# ECE411-Group6-V2.net
KiCad netlist of a schematic drawn in EAGLE
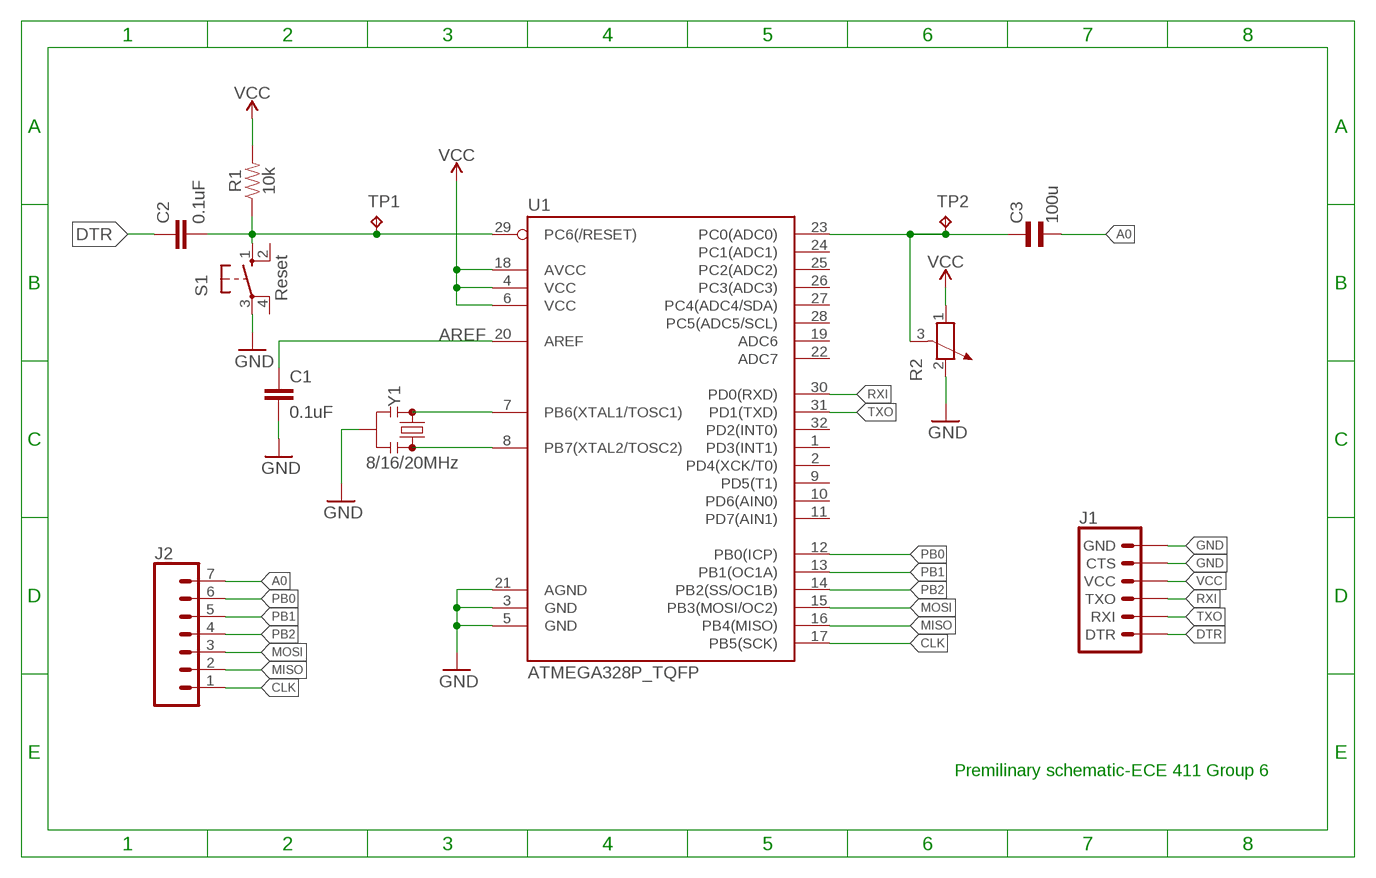
[diagram p0: schematic, sheet 1]

(export (version "E")
  (design (tool "Eeschema 10.0.6"))
  (components
    (comp (ref "C1")
      (value "0.1uF")
      (footprint "eagle-import:0603")
      (libsource (lib "eagle-import") (part "0.1UF-0603-25V-5%"))
    )
    (comp (ref "C2")
      (value "0.1uF")
      (footprint "eagle-import:0603")
      (libsource (lib "eagle-import") (part "0.1UF-0603-25V-5%"))
    )
    (comp (ref "C3")
      (value "100u")
      (footprint "eagle-import:EU25-10")
      (libsource (lib "eagle-import") (part "EL-BI25-10AXIAL"))
    )
    (comp (ref "J1")
      (value "6_PIN_SERIAL_TARGET")
      (footprint "eagle-import:1X06")
      (libsource (lib "eagle-import") (part "6_PIN_SERIAL_TARGET"))
    )
    (comp (ref "J2")
      (value "CONN_07")
      (footprint "eagle-import:1X07")
      (libsource (lib "eagle-import") (part "CONN_07"))
    )
    (comp (ref "R1")
      (value "10k")
      (footprint "eagle-import:0603")
      (libsource (lib "eagle-import") (part "10KOHM-0603-1/10W-1%"))
    )
    (comp (ref "R2")
      (value "POTENTIOMETER_PT-10")
      (footprint "eagle-import:PT-10")
      (libsource (lib "eagle-import") (part "POTENTIOMETER_PT-10"))
    )
    (comp (ref "S1")
      (value "Reset")
      (footprint "eagle-import:B3F-10XX")
      (fields (field (name "MPN") "B3F-1000"))
      (libsource (lib "eagle-import") (part "10-XX"))
    )
    (comp (ref "TP1")
      (value "TPB1,27")
      (footprint "eagle-import:B1,27")
      (libsource (lib "eagle-import") (part "TPB1,27"))
    )
    (comp (ref "TP2")
      (value "TPB1,27")
      (footprint "eagle-import:B1,27")
      (libsource (lib "eagle-import") (part "TPB1,27"))
    )
    (comp (ref "U1")
      (value "ATMEGA328P_TQFP")
      (footprint "eagle-import:TQFP32-08")
      (libsource (lib "eagle-import") (part "ATMEGA328P_TQFP"))
    )
    (comp (ref "Y1")
      (value "8/16/20MHz")
      (footprint "eagle-import:RESONATOR-SMD-3.2X1.3")
      (libsource (lib "eagle-import") (part "RESONATORSMD-3.2X1.3"))
    )
  )
  (nets
    (net (code "1") (name "/AREF") (class "Default")
      (node (ref "C1") (pin "1") (pinfunction "1_1") (pintype "passive"))
      (node (ref "U1") (pin "20") (pinfunction "AREF_20") (pintype "bidirectional"))
    )
    (net (code "2") (name "A0") (class "Default")
      (node (ref "C3") (pin "2") (pinfunction "2_2") (pintype "passive"))
      (node (ref "J2") (pin "7") (pinfunction "7_7") (pintype "passive"))
    )
    (net (code "3") (name "CLK") (class "Default")
      (node (ref "J2") (pin "1") (pinfunction "1_1") (pintype "passive"))
      (node (ref "U1") (pin "17") (pinfunction "PB5(SCK)_17") (pintype "bidirectional"))
    )
    (net (code "4") (name "DTR") (class "Default")
      (node (ref "C2") (pin "1") (pinfunction "1_1") (pintype "passive"))
      (node (ref "J1") (pin "1") (pinfunction "DTR_1") (pintype "passive"))
    )
    (net (code "5") (name "GND") (class "Default")
      (node (ref "C1") (pin "2") (pinfunction "2_2") (pintype "passive"))
      (node (ref "J1") (pin "5") (pinfunction "CTS_5") (pintype "passive"))
      (node (ref "J1") (pin "6") (pinfunction "GND_6") (pintype "passive"))
      (node (ref "R2") (pin "2") (pinfunction "2_2") (pintype "passive"))
      (node (ref "S1") (pin "3") (pinfunction "P_3") (pintype "passive"))
      (node (ref "U1") (pin "21") (pinfunction "AGND_21") (pintype "bidirectional"))
      (node (ref "U1") (pin "3") (pinfunction "GND_3") (pintype "bidirectional"))
      (node (ref "U1") (pin "5") (pinfunction "GND_5") (pintype "bidirectional"))
      (node (ref "Y1") (pin "2") (pinfunction "2_2") (pintype "passive"))
    )
    (net (code "6") (name "MISO") (class "Default")
      (node (ref "J2") (pin "2") (pinfunction "2_2") (pintype "passive"))
      (node (ref "U1") (pin "16") (pinfunction "PB4(MISO)_16") (pintype "bidirectional"))
    )
    (net (code "7") (name "MOSI") (class "Default")
      (node (ref "J2") (pin "3") (pinfunction "3_3") (pintype "passive"))
      (node (ref "U1") (pin "15") (pinfunction "PB3(MOSI/OC2)_15") (pintype "bidirectional"))
    )
    (net (code "8") (name "Net-(S1-S)") (class "Default")
      (node (ref "C2") (pin "2") (pinfunction "2_2") (pintype "passive"))
      (node (ref "R1") (pin "1") (pinfunction "1_1") (pintype "passive"))
      (node (ref "S1") (pin "1") (pinfunction "S_1") (pintype "passive"))
      (node (ref "TP1") (pin "TP") (pinfunction "TP_TP") (pintype "input"))
      (node (ref "U1") (pin "29") (pinfunction "PC6(/RESET)_29") (pintype "bidirectional"))
    )
    (net (code "9") (name "Net-(U1-PB6(XTAL1{slash}TOSC1))") (class "Default")
      (node (ref "U1") (pin "7") (pinfunction "PB6(XTAL1/TOSC1)_7") (pintype "bidirectional"))
      (node (ref "Y1") (pin "1") (pinfunction "1_1") (pintype "passive"))
    )
    (net (code "10") (name "Net-(U1-PB7(XTAL2{slash}TOSC2))") (class "Default")
      (node (ref "U1") (pin "8") (pinfunction "PB7(XTAL2/TOSC2)_8") (pintype "bidirectional"))
      (node (ref "Y1") (pin "3") (pinfunction "3_3") (pintype "passive"))
    )
    (net (code "11") (name "Net-(U1-PC0(ADC0))") (class "Default")
      (node (ref "C3") (pin "1") (pinfunction "1_1") (pintype "passive"))
      (node (ref "R2") (pin "3") (pinfunction "3_3") (pintype "passive"))
      (node (ref "TP2") (pin "TP") (pinfunction "TP_TP") (pintype "input"))
      (node (ref "U1") (pin "23") (pinfunction "PC0(ADC0)_23") (pintype "bidirectional"))
    )
    (net (code "12") (name "PB0") (class "Default")
      (node (ref "J2") (pin "6") (pinfunction "6_6") (pintype "passive"))
      (node (ref "U1") (pin "12") (pinfunction "PB0(ICP)_12") (pintype "bidirectional"))
    )
    (net (code "13") (name "PB1") (class "Default")
      (node (ref "J2") (pin "5") (pinfunction "5_5") (pintype "passive"))
      (node (ref "U1") (pin "13") (pinfunction "PB1(OC1A)_13") (pintype "bidirectional"))
    )
    (net (code "14") (name "PB2") (class "Default")
      (node (ref "J2") (pin "4") (pinfunction "4_4") (pintype "passive"))
      (node (ref "U1") (pin "14") (pinfunction "PB2(SS/OC1B)_14") (pintype "bidirectional"))
    )
    (net (code "15") (name "RXI") (class "Default")
      (node (ref "J1") (pin "3") (pinfunction "TXO_3") (pintype "passive"))
      (node (ref "U1") (pin "30") (pinfunction "PD0(RXD)_30") (pintype "bidirectional"))
    )
    (net (code "16") (name "TXO") (class "Default")
      (node (ref "J1") (pin "2") (pinfunction "RXI_2") (pintype "passive"))
      (node (ref "U1") (pin "31") (pinfunction "PD1(TXD)_31") (pintype "bidirectional"))
    )
    (net (code "17") (name "VCC") (class "Default")
      (node (ref "J1") (pin "4") (pinfunction "VCC_4") (pintype "passive"))
      (node (ref "R1") (pin "2") (pinfunction "2_2") (pintype "passive"))
      (node (ref "R2") (pin "1") (pinfunction "1_1") (pintype "passive"))
      (node (ref "U1") (pin "18") (pinfunction "AVCC_18") (pintype "bidirectional"))
      (node (ref "U1") (pin "4") (pinfunction "VCC_4") (pintype "bidirectional"))
      (node (ref "U1") (pin "6") (pinfunction "VCC_6") (pintype "bidirectional"))
    )
    (net (code "18") (name "unconnected-(S1-P1-Pad4)") (class "Default")
      (node (ref "S1") (pin "4") (pinfunction "P1_4") (pintype "passive"))
    )
    (net (code "19") (name "unconnected-(S1-S1-Pad2)") (class "Default")
      (node (ref "S1") (pin "2") (pinfunction "S1_2") (pintype "passive"))
    )
    (net (code "20") (name "unconnected-(U1-ADC6-Pad19)") (class "Default")
      (node (ref "U1") (pin "19") (pinfunction "ADC6_19") (pintype "bidirectional"))
    )
    (net (code "21") (name "unconnected-(U1-ADC7-Pad22)") (class "Default")
      (node (ref "U1") (pin "22") (pinfunction "ADC7_22") (pintype "bidirectional"))
    )
    (net (code "22") (name "unconnected-(U1-PC1(ADC1)-Pad24)") (class "Default")
      (node (ref "U1") (pin "24") (pinfunction "PC1(ADC1)_24") (pintype "bidirectional"))
    )
    (net (code "23") (name "unconnected-(U1-PC2(ADC2)-Pad25)") (class "Default")
      (node (ref "U1") (pin "25") (pinfunction "PC2(ADC2)_25") (pintype "bidirectional"))
    )
    (net (code "24") (name "unconnected-(U1-PC3(ADC3)-Pad26)") (class "Default")
      (node (ref "U1") (pin "26") (pinfunction "PC3(ADC3)_26") (pintype "bidirectional"))
    )
    (net (code "25") (name "unconnected-(U1-PC4(ADC4{slash}SDA)-Pad27)") (class "Default")
      (node (ref "U1") (pin "27") (pinfunction "PC4(ADC4/SDA)_27") (pintype "bidirectional"))
    )
    (net (code "26") (name "unconnected-(U1-PC5(ADC5{slash}SCL)-Pad28)") (class "Default")
      (node (ref "U1") (pin "28") (pinfunction "PC5(ADC5/SCL)_28") (pintype "bidirectional"))
    )
    (net (code "27") (name "unconnected-(U1-PD2(INT0)-Pad32)") (class "Default")
      (node (ref "U1") (pin "32") (pinfunction "PD2(INT0)_32") (pintype "bidirectional"))
    )
    (net (code "28") (name "unconnected-(U1-PD3(INT1)-Pad1)") (class "Default")
      (node (ref "U1") (pin "1") (pinfunction "PD3(INT1)_1") (pintype "bidirectional"))
    )
    (net (code "29") (name "unconnected-(U1-PD4(XCK{slash}T0)-Pad2)") (class "Default")
      (node (ref "U1") (pin "2") (pinfunction "PD4(XCK/T0)_2") (pintype "bidirectional"))
    )
    (net (code "30") (name "unconnected-(U1-PD5(T1)-Pad9)") (class "Default")
      (node (ref "U1") (pin "9") (pinfunction "PD5(T1)_9") (pintype "bidirectional"))
    )
    (net (code "31") (name "unconnected-(U1-PD6(AIN0)-Pad10)") (class "Default")
      (node (ref "U1") (pin "10") (pinfunction "PD6(AIN0)_10") (pintype "bidirectional"))
    )
    (net (code "32") (name "unconnected-(U1-PD7(AIN1)-Pad11)") (class "Default")
      (node (ref "U1") (pin "11") (pinfunction "PD7(AIN1)_11") (pintype "bidirectional"))
    )
  )
)
